# input_signal_conditioning.net
KiCad netlist of a schematic drawn in Altium Designer
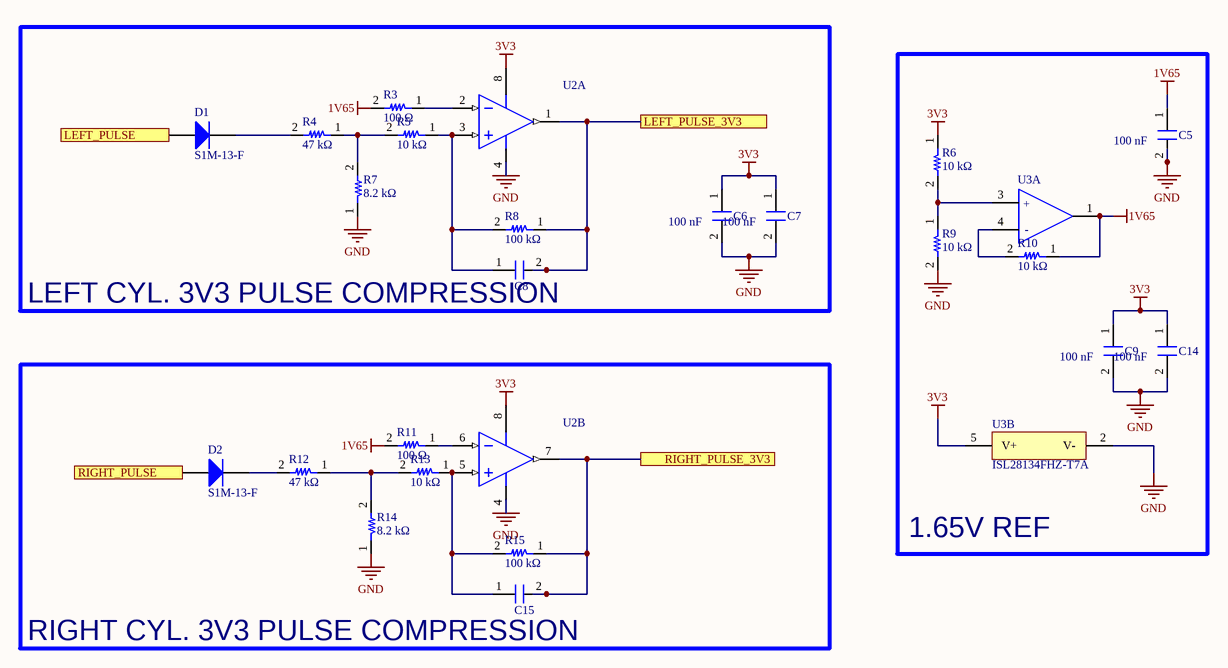
[diagram p0: input_signal_conditioning.SchDoc]

(export (version "E")
  (design (tool "Eeschema 10.0.6"))
  (components
    (comp (ref "C5")
      (value "100 nF")
      (footprint "0402_fp")
      (fields (field (name "Comment") "Capacitor_0402"))
      (libsource (lib "0402_sch") (part "Capacitor_0402"))
    )
    (comp (ref "C6")
      (value "100 nF")
      (footprint "0402_fp")
      (fields (field (name "Comment") "Capacitor_0402"))
      (libsource (lib "0402_sch") (part "Capacitor_0402"))
    )
    (comp (ref "C7")
      (value "100 nF")
      (footprint "0402_fp")
      (fields (field (name "Comment") "Capacitor_0402"))
      (libsource (lib "0402_sch") (part "Capacitor_0402"))
    )
    (comp (ref "C8")
      (value "Capacitor_0402")
      (footprint "0402_fp")
      (libsource (lib "0402_sch") (part "Capacitor_0402"))
    )
    (comp (ref "C9")
      (value "100 nF")
      (footprint "0402_fp")
      (fields (field (name "Comment") "Capacitor_0402"))
      (libsource (lib "0402_sch") (part "Capacitor_0402"))
    )
    (comp (ref "C14")
      (value "100 nF")
      (footprint "0402_fp")
      (fields (field (name "Comment") "Capacitor_0402"))
      (libsource (lib "0402_sch") (part "Capacitor_0402"))
    )
    (comp (ref "C15")
      (value "Capacitor_0402")
      (footprint "0402_fp")
      (libsource (lib "0402_sch") (part "Capacitor_0402"))
    )
    (comp (ref "D1")
      (value "S1M-13-F")
      (footprint "DIOD-S1M-13-F-SMA-2_V")
      (fields (field (name "MANUFACTURER") "Diodes Inc"))
      (libsource (lib "Altium Content Vault") (part "DIOD-D-A1K2-2"))
    )
    (comp (ref "D2")
      (value "S1M-13-F")
      (footprint "DIOD-S1M-13-F-SMA-2_V")
      (fields (field (name "MANUFACTURER") "Diodes Inc"))
      (libsource (lib "Altium Content Vault") (part "DIOD-D-A1K2-2"))
    )
    (comp (ref "R3")
      (value "100 Ω")
      (footprint "0402_fp")
      (fields (field (name "Comment") "Resistor_0402"))
      (libsource (lib "0402_sch") (part "Resistor_0402"))
    )
    (comp (ref "R4")
      (value "47 kΩ")
      (footprint "0402_fp")
      (fields (field (name "Comment") "Resistor_0402"))
      (libsource (lib "0402_sch") (part "Resistor_0402"))
    )
    (comp (ref "R5")
      (value "10 kΩ")
      (footprint "0402_fp")
      (fields (field (name "Comment") "Resistor_0402"))
      (libsource (lib "0402_sch") (part "Resistor_0402"))
    )
    (comp (ref "R6")
      (value "10 kΩ")
      (footprint "0402_fp")
      (fields (field (name "Comment") "Resistor_0402"))
      (libsource (lib "0402_sch") (part "Resistor_0402"))
    )
    (comp (ref "R7")
      (value "8.2 kΩ")
      (footprint "0402_fp")
      (fields (field (name "Comment") "Resistor_0402"))
      (libsource (lib "0402_sch") (part "Resistor_0402"))
    )
    (comp (ref "R8")
      (value "100 kΩ")
      (footprint "0402_fp")
      (fields (field (name "Comment") "Resistor_0402"))
      (libsource (lib "0402_sch") (part "Resistor_0402"))
    )
    (comp (ref "R9")
      (value "10 kΩ")
      (footprint "0402_fp")
      (fields (field (name "Comment") "Resistor_0402"))
      (libsource (lib "0402_sch") (part "Resistor_0402"))
    )
    (comp (ref "R10")
      (value "10 kΩ")
      (footprint "0402_fp")
      (fields (field (name "Comment") "Resistor_0402"))
      (libsource (lib "0402_sch") (part "Resistor_0402"))
    )
    (comp (ref "R11")
      (value "100 Ω")
      (footprint "0402_fp")
      (fields (field (name "Comment") "Resistor_0402"))
      (libsource (lib "0402_sch") (part "Resistor_0402"))
    )
    (comp (ref "R12")
      (value "47 kΩ")
      (footprint "0402_fp")
      (fields (field (name "Comment") "Resistor_0402"))
      (libsource (lib "0402_sch") (part "Resistor_0402"))
    )
    (comp (ref "R13")
      (value "10 kΩ")
      (footprint "0402_fp")
      (fields (field (name "Comment") "Resistor_0402"))
      (libsource (lib "0402_sch") (part "Resistor_0402"))
    )
    (comp (ref "R14")
      (value "8.2 kΩ")
      (footprint "0402_fp")
      (fields (field (name "Comment") "Resistor_0402"))
      (libsource (lib "0402_sch") (part "Resistor_0402"))
    )
    (comp (ref "R15")
      (value "100 kΩ")
      (footprint "0402_fp")
      (fields (field (name "Comment") "Resistor_0402"))
      (libsource (lib "0402_sch") (part "Resistor_0402"))
    )
    (comp (ref "U2")
      (value "LM358MX")
      (footprint "D0008A_M")
      (description "Low Power Dual Operational Amplifier, 8-pin Narrow SOIC")
      (fields (field (name "MANUFACTURER") "Texas Instruments"))
      (libsource (lib "Altium Content Vault") (part "AMP-OPA-LM158-8"))
    )
    (comp (ref "U3")
      (value "ISL28134FHZ-T7A")
      (footprint "P5_064A_MFG")
      (description "5V Ultra Low Noise, Zero Drift Rail-to-Rail Precision Op Amp")
      (libsource (lib "Altium Content Vault") (part "f9e763aa6c1cb993df744a22cc12b03"))
    )
  )
  (nets
    (net (code "1") (name "/LEFT_PULSE") (class "Default")
      (node (ref "D1") (pin "1") (pinfunction "A_1") (pintype "passive"))
    )
    (net (code "2") (name "/LEFT_PULSE_3V3") (class "Default")
      (node (ref "C8") (pin "2") (pinfunction "2_2") (pintype "passive"))
      (node (ref "R8") (pin "1") (pinfunction "1_1") (pintype "passive"))
      (node (ref "U2") (pin "1") (pinfunction "OUTA_1") (pintype "output"))
    )
    (net (code "3") (name "/RIGHT_PULSE") (class "Default")
      (node (ref "D2") (pin "1") (pinfunction "A_1") (pintype "passive"))
    )
    (net (code "4") (name "/RIGHT_PULSE_3V3") (class "Default")
      (node (ref "C15") (pin "2") (pinfunction "2_2") (pintype "passive"))
      (node (ref "R15") (pin "1") (pinfunction "1_1") (pintype "passive"))
      (node (ref "U2") (pin "7") (pinfunction "OUTB_7") (pintype "output"))
    )
    (net (code "5") (name "1V65") (class "Default")
      (node (ref "C5") (pin "1") (pinfunction "1_1") (pintype "passive"))
      (node (ref "R10") (pin "1") (pinfunction "1_1") (pintype "passive"))
      (node (ref "R11") (pin "2") (pinfunction "2_2") (pintype "passive"))
      (node (ref "R3") (pin "2") (pinfunction "2_2") (pintype "passive"))
      (node (ref "U3") (pin "1") (pinfunction "OUT_1") (pintype "passive"))
    )
    (net (code "6") (name "3V3") (class "Default")
      (node (ref "C14") (pin "1") (pinfunction "1_1") (pintype "passive"))
      (node (ref "C6") (pin "1") (pinfunction "1_1") (pintype "passive"))
      (node (ref "C7") (pin "1") (pinfunction "1_1") (pintype "passive"))
      (node (ref "C9") (pin "1") (pinfunction "1_1") (pintype "passive"))
      (node (ref "R6") (pin "1") (pinfunction "1_1") (pintype "passive"))
      (node (ref "U2") (pin "8") (pinfunction "V+_8") (pintype "power_in"))
      (node (ref "U3") (pin "5") (pinfunction "V+_5") (pintype "power_in"))
    )
    (net (code "7") (name "GND") (class "Default")
      (node (ref "C14") (pin "2") (pinfunction "2_2") (pintype "passive"))
      (node (ref "C5") (pin "2") (pinfunction "2_2") (pintype "passive"))
      (node (ref "C6") (pin "2") (pinfunction "2_2") (pintype "passive"))
      (node (ref "C7") (pin "2") (pinfunction "2_2") (pintype "passive"))
      (node (ref "C9") (pin "2") (pinfunction "2_2") (pintype "passive"))
      (node (ref "R14") (pin "1") (pinfunction "1_1") (pintype "passive"))
      (node (ref "R7") (pin "1") (pinfunction "1_1") (pintype "passive"))
      (node (ref "R9") (pin "2") (pinfunction "2_2") (pintype "passive"))
      (node (ref "U2") (pin "4") (pinfunction "GND_4") (pintype "power_in"))
      (node (ref "U3") (pin "2") (pinfunction "V-_2") (pintype "power_in"))
    )
    (net (code "8") (name "Net-(D1-K)") (class "Default")
      (node (ref "D1") (pin "2") (pinfunction "K_2") (pintype "passive"))
      (node (ref "R4") (pin "2") (pinfunction "2_2") (pintype "passive"))
    )
    (net (code "9") (name "Net-(D2-K)") (class "Default")
      (node (ref "D2") (pin "2") (pinfunction "K_2") (pintype "passive"))
      (node (ref "R12") (pin "2") (pinfunction "2_2") (pintype "passive"))
    )
    (net (code "10") (name "Net-(R4-Pad1)") (class "Default")
      (node (ref "R4") (pin "1") (pinfunction "1_1") (pintype "passive"))
      (node (ref "R5") (pin "2") (pinfunction "2_2") (pintype "passive"))
      (node (ref "R7") (pin "2") (pinfunction "2_2") (pintype "passive"))
    )
    (net (code "11") (name "Net-(R12-Pad1)") (class "Default")
      (node (ref "R12") (pin "1") (pinfunction "1_1") (pintype "passive"))
      (node (ref "R13") (pin "2") (pinfunction "2_2") (pintype "passive"))
      (node (ref "R14") (pin "2") (pinfunction "2_2") (pintype "passive"))
    )
    (net (code "12") (name "Net-(U2A-INA+)") (class "Default")
      (node (ref "C8") (pin "1") (pinfunction "1_1") (pintype "passive"))
      (node (ref "R5") (pin "1") (pinfunction "1_1") (pintype "passive"))
      (node (ref "R8") (pin "2") (pinfunction "2_2") (pintype "passive"))
      (node (ref "U2") (pin "3") (pinfunction "INA+_3") (pintype "input"))
    )
    (net (code "13") (name "Net-(U2A-INA-)") (class "Default")
      (node (ref "R3") (pin "1") (pinfunction "1_1") (pintype "passive"))
      (node (ref "U2") (pin "2") (pinfunction "INA-_2") (pintype "input"))
    )
    (net (code "14") (name "Net-(U2B-INB+)") (class "Default")
      (node (ref "C15") (pin "1") (pinfunction "1_1") (pintype "passive"))
      (node (ref "R13") (pin "1") (pinfunction "1_1") (pintype "passive"))
      (node (ref "R15") (pin "2") (pinfunction "2_2") (pintype "passive"))
      (node (ref "U2") (pin "5") (pinfunction "INB+_5") (pintype "input"))
    )
    (net (code "15") (name "Net-(U2B-INB-)") (class "Default")
      (node (ref "R11") (pin "1") (pinfunction "1_1") (pintype "passive"))
      (node (ref "U2") (pin "6") (pinfunction "INB-_6") (pintype "input"))
    )
    (net (code "16") (name "Net-(U3A-IN+)") (class "Default")
      (node (ref "R6") (pin "2") (pinfunction "2_2") (pintype "passive"))
      (node (ref "R9") (pin "1") (pinfunction "1_1") (pintype "passive"))
      (node (ref "U3") (pin "3") (pinfunction "IN+_3") (pintype "tri_state"))
    )
    (net (code "17") (name "Net-(U3A-IN-)") (class "Default")
      (node (ref "R10") (pin "2") (pinfunction "2_2") (pintype "passive"))
      (node (ref "U3") (pin "4") (pinfunction "IN-_4") (pintype "tri_state"))
    )
  )
)
